# smalAtmBoard.net
KiCad netlist of a schematic drawn in EAGLE
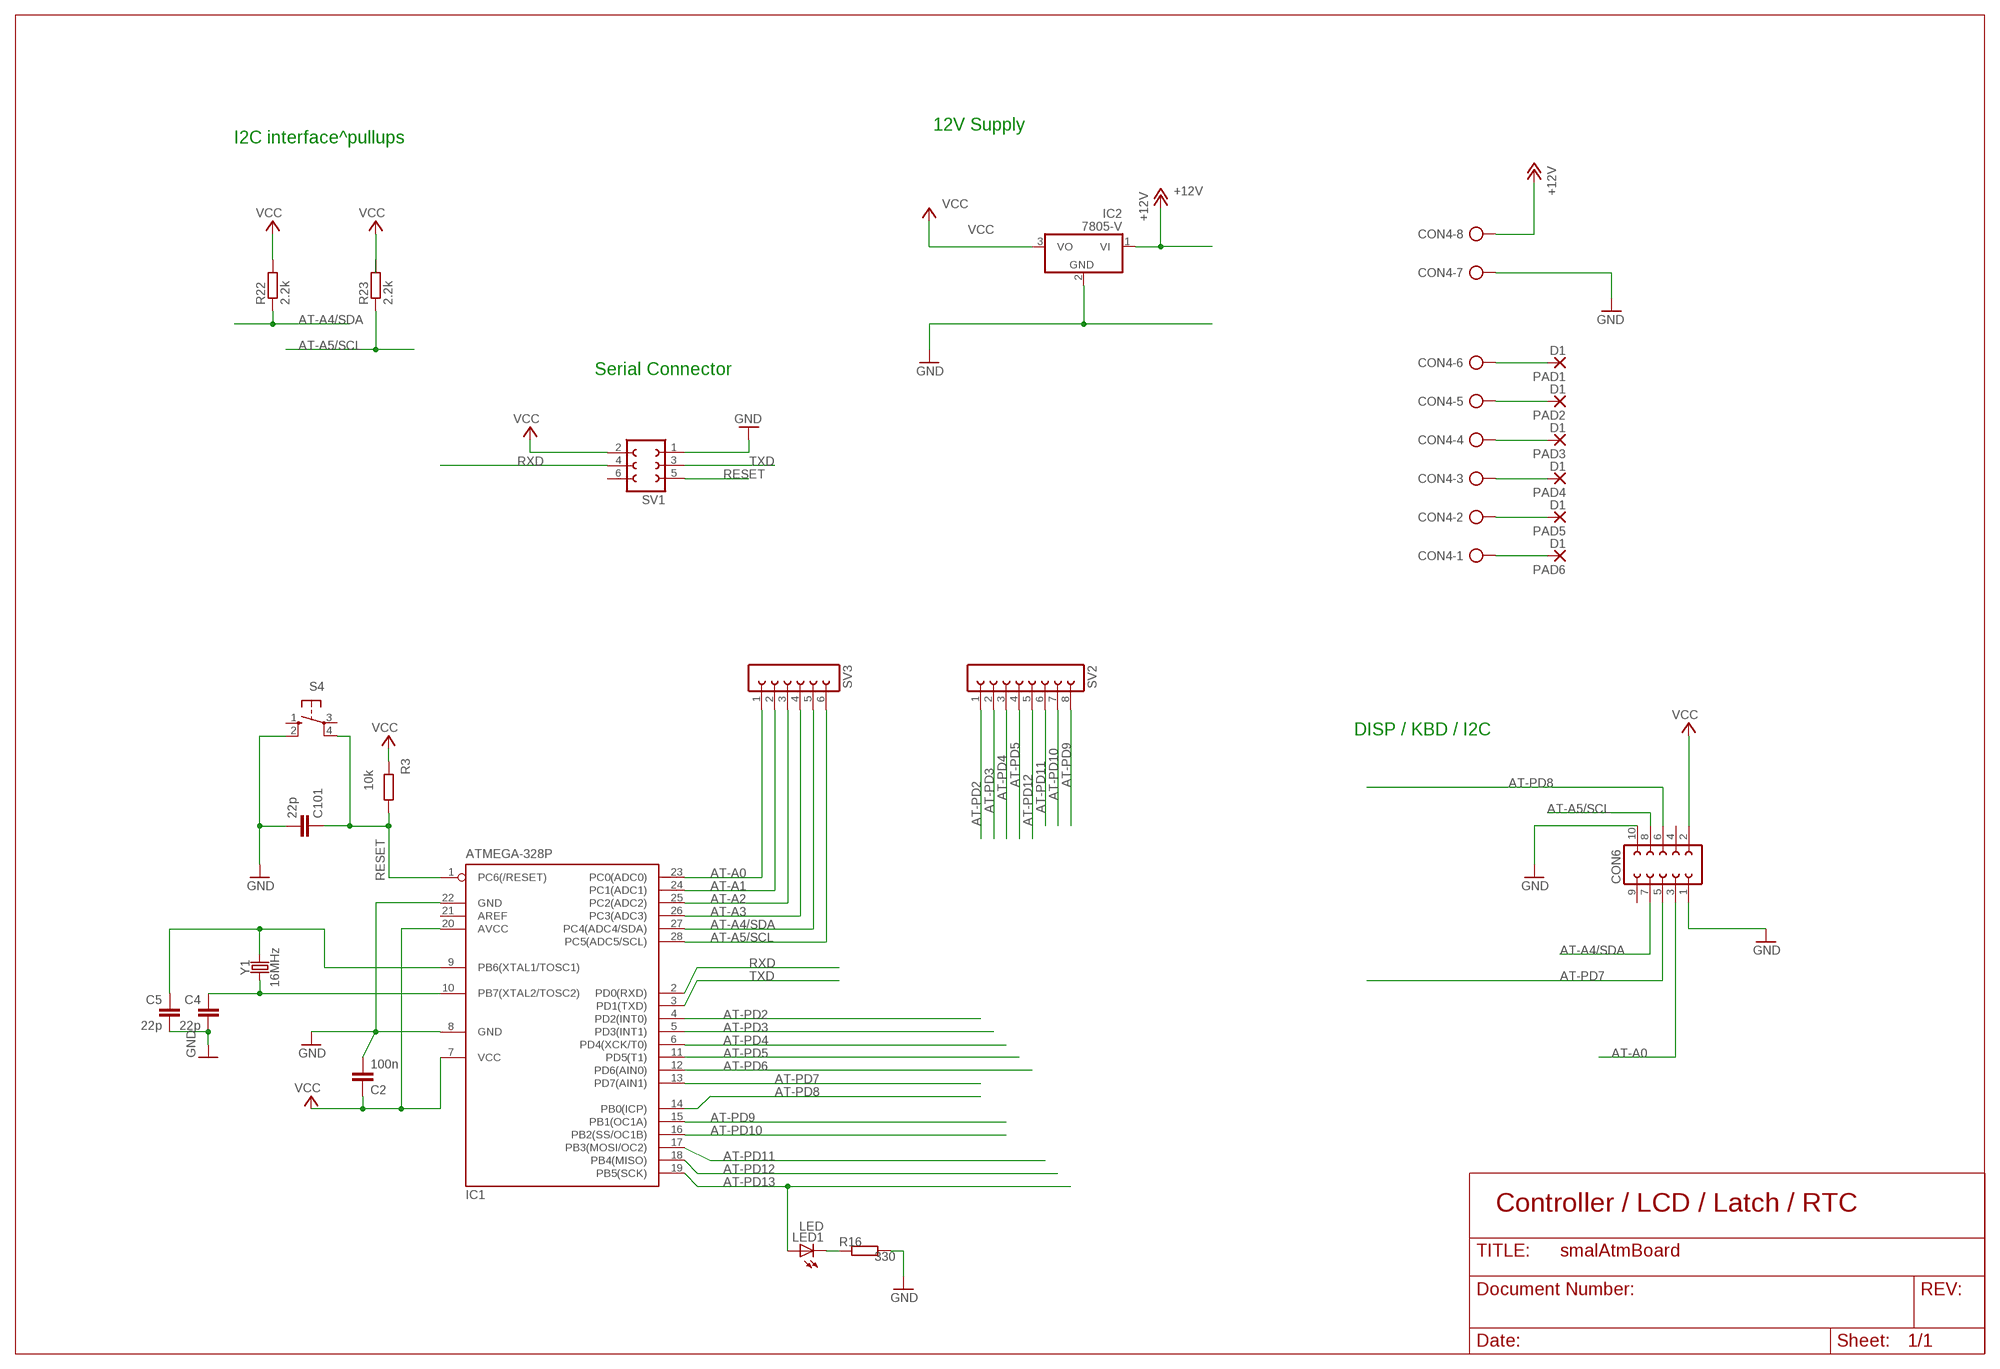
[diagram p0: schematic, sheet 1]

(export (version "E")
  (design (tool "Eeschema 10.0.6"))
  (components
    (comp (ref "C2")
      (value "100n")
      (footprint "eagle-import:C050-024X044")
      (libsource (lib "eagle-import") (part "C-55MM"))
    )
    (comp (ref "C4")
      (value "22p")
      (footprint "eagle-import:C050-024X044")
      (libsource (lib "eagle-import") (part "C-55MM"))
    )
    (comp (ref "C5")
      (value "22p")
      (footprint "eagle-import:C050-024X044")
      (libsource (lib "eagle-import") (part "C-55MM"))
    )
    (comp (ref "C101")
      (value "22p")
      (footprint "eagle-import:C050-024X044")
      (libsource (lib "eagle-import") (part "C-55MM"))
    )
    (comp (ref "CON4")
      (value "AK300/8")
      (footprint "eagle-import:AK300_8")
      (libsource (lib "eagle-import") (part "AK300/8"))
    )
    (comp (ref "CON6")
      (value "FE05-2")
      (footprint "eagle-import:FE05-2")
      (libsource (lib "eagle-import") (part "FE05-2"))
    )
    (comp (ref "IC1")
      (value "ATMEGA-328P")
      (footprint "eagle-import:DIL28-3")
      (libsource (lib "eagle-import") (part "ATMEGA-XX8-P"))
    )
    (comp (ref "IC2")
      (value "7805-V")
      (footprint "eagle-import:TO220V")
      (libsource (lib "eagle-import") (part "7805-V"))
    )
    (comp (ref "LED1")
      (value "LED")
      (footprint "eagle-import:LED_LD260")
      (libsource (lib "eagle-import") (part "LED"))
    )
    (comp (ref "PAD1")
      (value "D1")
      (footprint "eagle-import:PAD1,6_0,8")
      (libsource (lib "eagle-import") (part "PAD1,6/0,8"))
    )
    (comp (ref "PAD2")
      (value "D1")
      (footprint "eagle-import:PAD1,6_0,8")
      (libsource (lib "eagle-import") (part "PAD1,6/0,8"))
    )
    (comp (ref "PAD3")
      (value "D1")
      (footprint "eagle-import:PAD1,6_0,8")
      (libsource (lib "eagle-import") (part "PAD1,6/0,8"))
    )
    (comp (ref "PAD4")
      (value "D1")
      (footprint "eagle-import:PAD1,6_0,8")
      (libsource (lib "eagle-import") (part "PAD1,6/0,8"))
    )
    (comp (ref "PAD5")
      (value "D1")
      (footprint "eagle-import:PAD1,6_0,8")
      (libsource (lib "eagle-import") (part "PAD1,6/0,8"))
    )
    (comp (ref "PAD6")
      (value "D1")
      (footprint "eagle-import:PAD1,6_0,8")
      (libsource (lib "eagle-import") (part "PAD1,6/0,8"))
    )
    (comp (ref "R3")
      (value "10k")
      (footprint "eagle-import:R_0207_2V")
      (libsource (lib "eagle-import") (part "R-EU_0207/2V"))
    )
    (comp (ref "R16")
      (value "330")
      (footprint "eagle-import:R_0207_2V")
      (libsource (lib "eagle-import") (part "R-EU_0207/2V"))
    )
    (comp (ref "R22")
      (value "2.2k")
      (footprint "eagle-import:R_0207_2V")
      (libsource (lib "eagle-import") (part "R-EU_0207/2V"))
    )
    (comp (ref "R23")
      (value "2.2k")
      (footprint "eagle-import:R_0207_2V")
      (libsource (lib "eagle-import") (part "R-EU_0207/2V"))
    )
    (comp (ref "S4")
      (value "10-XX")
      (footprint "eagle-import:B3F-10XX")
      (fields (field (name "MPN") "B3F-1000"))
      (libsource (lib "eagle-import") (part "10-XX"))
    )
    (comp (ref "SV1")
      (value "FE03-2FE03-2RAW")
      (footprint "eagle-import:FE03-2RAW")
      (libsource (lib "eagle-import") (part "FE03-2FE03-2RAW"))
    )
    (comp (ref "SV2")
      (value "FE08-1")
      (footprint "eagle-import:FE08")
      (libsource (lib "eagle-import") (part "FE08-1"))
    )
    (comp (ref "SV3")
      (value "FE06-1")
      (footprint "eagle-import:FE06")
      (libsource (lib "eagle-import") (part "FE06-1"))
    )
    (comp (ref "Y1")
      (value "16MHz")
      (footprint "eagle-import:HC49US")
      (libsource (lib "eagle-import") (part "CRYSTALPTH-HC49US"))
    )
  )
  (nets
    (net (code "1") (name "+12V") (class "Default")
      (node (ref "CON4") (pin "8") (pinfunction "KL_8") (pintype "passive"))
      (node (ref "IC2") (pin "1") (pinfunction "VI_1") (pintype "power_in"))
    )
    (net (code "2") (name "/AT-A0") (class "Default")
      (node (ref "CON6") (pin "3") (pinfunction "3_3") (pintype "passive"))
      (node (ref "IC1") (pin "23") (pinfunction "PC0(ADC0)_23") (pintype "bidirectional"))
      (node (ref "SV3") (pin "1") (pinfunction "1_1") (pintype "passive"))
    )
    (net (code "3") (name "/AT-A1") (class "Default")
      (node (ref "IC1") (pin "24") (pinfunction "PC1(ADC1)_24") (pintype "bidirectional"))
      (node (ref "SV3") (pin "2") (pinfunction "2_2") (pintype "passive"))
    )
    (net (code "4") (name "/AT-A2") (class "Default")
      (node (ref "IC1") (pin "25") (pinfunction "PC2(ADC2)_25") (pintype "bidirectional"))
      (node (ref "SV3") (pin "3") (pinfunction "3_3") (pintype "passive"))
    )
    (net (code "5") (name "/AT-A3") (class "Default")
      (node (ref "IC1") (pin "26") (pinfunction "PC3(ADC3)_26") (pintype "bidirectional"))
      (node (ref "SV3") (pin "4") (pinfunction "4_4") (pintype "passive"))
    )
    (net (code "6") (name "/AT-A4{slash}SDA") (class "Default")
      (node (ref "CON6") (pin "7") (pinfunction "7_7") (pintype "passive"))
      (node (ref "IC1") (pin "27") (pinfunction "PC4(ADC4/SDA)_27") (pintype "bidirectional"))
      (node (ref "R22") (pin "1") (pinfunction "1_1") (pintype "passive"))
      (node (ref "SV3") (pin "5") (pinfunction "5_5") (pintype "passive"))
    )
    (net (code "7") (name "/AT-A5{slash}SCL") (class "Default")
      (node (ref "CON6") (pin "8") (pinfunction "8_8") (pintype "passive"))
      (node (ref "IC1") (pin "28") (pinfunction "PC5(ADC5/SCL)_28") (pintype "bidirectional"))
      (node (ref "R23") (pin "1") (pinfunction "1_1") (pintype "passive"))
      (node (ref "SV3") (pin "6") (pinfunction "6_6") (pintype "passive"))
    )
    (net (code "8") (name "/AT-PD2") (class "Default")
      (node (ref "IC1") (pin "4") (pinfunction "PD2(INT0)_4") (pintype "bidirectional"))
      (node (ref "SV2") (pin "1") (pinfunction "1_1") (pintype "passive"))
    )
    (net (code "9") (name "/AT-PD3") (class "Default")
      (node (ref "IC1") (pin "5") (pinfunction "PD3(INT1)_5") (pintype "bidirectional"))
      (node (ref "SV2") (pin "2") (pinfunction "2_2") (pintype "passive"))
    )
    (net (code "10") (name "/AT-PD4") (class "Default")
      (node (ref "IC1") (pin "6") (pinfunction "PD4(XCK/T0)_6") (pintype "bidirectional"))
      (node (ref "SV2") (pin "3") (pinfunction "3_3") (pintype "passive"))
    )
    (net (code "11") (name "/AT-PD5") (class "Default")
      (node (ref "IC1") (pin "11") (pinfunction "PD5(T1)_11") (pintype "bidirectional"))
      (node (ref "SV2") (pin "4") (pinfunction "4_4") (pintype "passive"))
    )
    (net (code "12") (name "/AT-PD6") (class "Default")
      (node (ref "IC1") (pin "12") (pinfunction "PD6(AIN0)_12") (pintype "bidirectional"))
    )
    (net (code "13") (name "/AT-PD7") (class "Default")
      (node (ref "CON6") (pin "5") (pinfunction "5_5") (pintype "passive"))
      (node (ref "IC1") (pin "13") (pinfunction "PD7(AIN1)_13") (pintype "bidirectional"))
    )
    (net (code "14") (name "/AT-PD8") (class "Default")
      (node (ref "CON6") (pin "6") (pinfunction "6_6") (pintype "passive"))
      (node (ref "IC1") (pin "14") (pinfunction "PB0(ICP)_14") (pintype "bidirectional"))
    )
    (net (code "15") (name "/AT-PD9") (class "Default")
      (node (ref "IC1") (pin "15") (pinfunction "PB1(OC1A)_15") (pintype "bidirectional"))
      (node (ref "SV2") (pin "8") (pinfunction "8_8") (pintype "passive"))
    )
    (net (code "16") (name "/AT-PD10") (class "Default")
      (node (ref "IC1") (pin "16") (pinfunction "PB2(SS/OC1B)_16") (pintype "bidirectional"))
      (node (ref "SV2") (pin "7") (pinfunction "7_7") (pintype "passive"))
    )
    (net (code "17") (name "/AT-PD11") (class "Default")
      (node (ref "IC1") (pin "17") (pinfunction "PB3(MOSI/OC2)_17") (pintype "bidirectional"))
      (node (ref "SV2") (pin "6") (pinfunction "6_6") (pintype "passive"))
    )
    (net (code "18") (name "/AT-PD12") (class "Default")
      (node (ref "IC1") (pin "18") (pinfunction "PB4(MISO)_18") (pintype "bidirectional"))
      (node (ref "SV2") (pin "5") (pinfunction "5_5") (pintype "passive"))
    )
    (net (code "19") (name "/AT-PD13") (class "Default")
      (node (ref "IC1") (pin "19") (pinfunction "PB5(SCK)_19") (pintype "bidirectional"))
      (node (ref "LED1") (pin "A") (pinfunction "A_A") (pintype "passive"))
    )
    (net (code "20") (name "/RESET") (class "Default")
      (node (ref "C101") (pin "1") (pinfunction "1_1") (pintype "passive"))
      (node (ref "IC1") (pin "1") (pinfunction "PC6(/RESET)_1") (pintype "bidirectional"))
      (node (ref "R3") (pin "2") (pinfunction "2_2") (pintype "passive"))
      (node (ref "S4") (pin "4") (pinfunction "P1_4") (pintype "passive"))
      (node (ref "SV1") (pin "5") (pinfunction "5_5") (pintype "passive"))
    )
    (net (code "21") (name "/RXD") (class "Default")
      (node (ref "IC1") (pin "2") (pinfunction "PD0(RXD)_2") (pintype "bidirectional"))
      (node (ref "SV1") (pin "4") (pinfunction "4_4") (pintype "passive"))
    )
    (net (code "22") (name "/TXD") (class "Default")
      (node (ref "IC1") (pin "3") (pinfunction "PD1(TXD)_3") (pintype "bidirectional"))
      (node (ref "SV1") (pin "3") (pinfunction "3_3") (pintype "passive"))
    )
    (net (code "23") (name "GND") (class "Default")
      (node (ref "C101") (pin "2") (pinfunction "2_2") (pintype "passive"))
      (node (ref "C2") (pin "2") (pinfunction "2_2") (pintype "passive"))
      (node (ref "C4") (pin "2") (pinfunction "2_2") (pintype "passive"))
      (node (ref "C5") (pin "2") (pinfunction "2_2") (pintype "passive"))
      (node (ref "CON4") (pin "7") (pinfunction "KL_7") (pintype "passive"))
      (node (ref "CON6") (pin "1") (pinfunction "1_1") (pintype "passive"))
      (node (ref "CON6") (pin "10") (pinfunction "10_10") (pintype "passive"))
      (node (ref "IC1") (pin "22") (pinfunction "GND_22") (pintype "power_in"))
      (node (ref "IC1") (pin "8") (pinfunction "GND_8") (pintype "power_in"))
      (node (ref "IC2") (pin "2") (pinfunction "GND_2") (pintype "power_in"))
      (node (ref "R16") (pin "1") (pinfunction "1_1") (pintype "passive"))
      (node (ref "S4") (pin "2") (pinfunction "S1_2") (pintype "passive"))
      (node (ref "SV1") (pin "1") (pinfunction "1_1") (pintype "passive"))
    )
    (net (code "24") (name "Net-(CON4A-KL)") (class "Default")
      (node (ref "CON4") (pin "1") (pinfunction "KL_1") (pintype "passive"))
      (node (ref "PAD6") (pin "1") (pinfunction "P_1") (pintype "passive"))
    )
    (net (code "25") (name "Net-(CON4B-KL)") (class "Default")
      (node (ref "CON4") (pin "2") (pinfunction "KL_2") (pintype "passive"))
      (node (ref "PAD5") (pin "1") (pinfunction "P_1") (pintype "passive"))
    )
    (net (code "26") (name "Net-(CON4C-KL)") (class "Default")
      (node (ref "CON4") (pin "3") (pinfunction "KL_3") (pintype "passive"))
      (node (ref "PAD4") (pin "1") (pinfunction "P_1") (pintype "passive"))
    )
    (net (code "27") (name "Net-(CON4D-KL)") (class "Default")
      (node (ref "CON4") (pin "4") (pinfunction "KL_4") (pintype "passive"))
      (node (ref "PAD3") (pin "1") (pinfunction "P_1") (pintype "passive"))
    )
    (net (code "28") (name "Net-(CON4E-KL)") (class "Default")
      (node (ref "CON4") (pin "5") (pinfunction "KL_5") (pintype "passive"))
      (node (ref "PAD2") (pin "1") (pinfunction "P_1") (pintype "passive"))
    )
    (net (code "29") (name "Net-(CON4F-KL)") (class "Default")
      (node (ref "CON4") (pin "6") (pinfunction "KL_6") (pintype "passive"))
      (node (ref "PAD1") (pin "1") (pinfunction "P_1") (pintype "passive"))
    )
    (net (code "30") (name "Net-(IC1-PB6(XTAL1{slash}TOSC1))") (class "Default")
      (node (ref "C5") (pin "1") (pinfunction "1_1") (pintype "passive"))
      (node (ref "IC1") (pin "9") (pinfunction "PB6(XTAL1/TOSC1)_9") (pintype "bidirectional"))
      (node (ref "Y1") (pin "2") (pinfunction "2_2") (pintype "passive"))
    )
    (net (code "31") (name "Net-(IC1-PB7(XTAL2{slash}TOSC2))") (class "Default")
      (node (ref "C4") (pin "1") (pinfunction "1_1") (pintype "passive"))
      (node (ref "IC1") (pin "10") (pinfunction "PB7(XTAL2/TOSC2)_10") (pintype "bidirectional"))
      (node (ref "Y1") (pin "1") (pinfunction "1_1") (pintype "passive"))
    )
    (net (code "32") (name "Net-(LED1-C)") (class "Default")
      (node (ref "LED1") (pin "K") (pinfunction "C_K") (pintype "passive"))
      (node (ref "R16") (pin "2") (pinfunction "2_2") (pintype "passive"))
    )
    (net (code "33") (name "VCC") (class "Default")
      (node (ref "C2") (pin "1") (pinfunction "1_1") (pintype "passive"))
      (node (ref "CON6") (pin "2") (pinfunction "2_2") (pintype "passive"))
      (node (ref "IC1") (pin "20") (pinfunction "AVCC_20") (pintype "power_in"))
      (node (ref "IC1") (pin "7") (pinfunction "VCC_7") (pintype "power_in"))
      (node (ref "IC2") (pin "3") (pinfunction "VO_3") (pintype "power_in"))
      (node (ref "R22") (pin "2") (pinfunction "2_2") (pintype "passive"))
      (node (ref "R23") (pin "2") (pinfunction "2_2") (pintype "passive"))
      (node (ref "R3") (pin "1") (pinfunction "1_1") (pintype "passive"))
      (node (ref "SV1") (pin "2") (pinfunction "2_2") (pintype "passive"))
    )
    (net (code "34") (name "unconnected-(CON6-Pad4)") (class "Default")
      (node (ref "CON6") (pin "4") (pinfunction "4_4") (pintype "passive"))
    )
    (net (code "35") (name "unconnected-(CON6-Pad9)") (class "Default")
      (node (ref "CON6") (pin "9") (pinfunction "9_9") (pintype "passive"))
    )
    (net (code "36") (name "unconnected-(IC1-AREF-Pad21)") (class "Default")
      (node (ref "IC1") (pin "21") (pinfunction "AREF_21") (pintype "passive"))
    )
    (net (code "37") (name "unconnected-(S4-P-Pad3)") (class "Default")
      (node (ref "S4") (pin "3") (pinfunction "P_3") (pintype "passive"))
    )
    (net (code "38") (name "unconnected-(S4-S-Pad1)") (class "Default")
      (node (ref "S4") (pin "1") (pinfunction "S_1") (pintype "passive"))
    )
    (net (code "39") (name "unconnected-(SV1-Pad6)") (class "Default")
      (node (ref "SV1") (pin "6") (pinfunction "6_6") (pintype "passive"))
    )
  )
)
